# LOGIC.net
KiCad netlist of a schematic drawn in Altium Designer
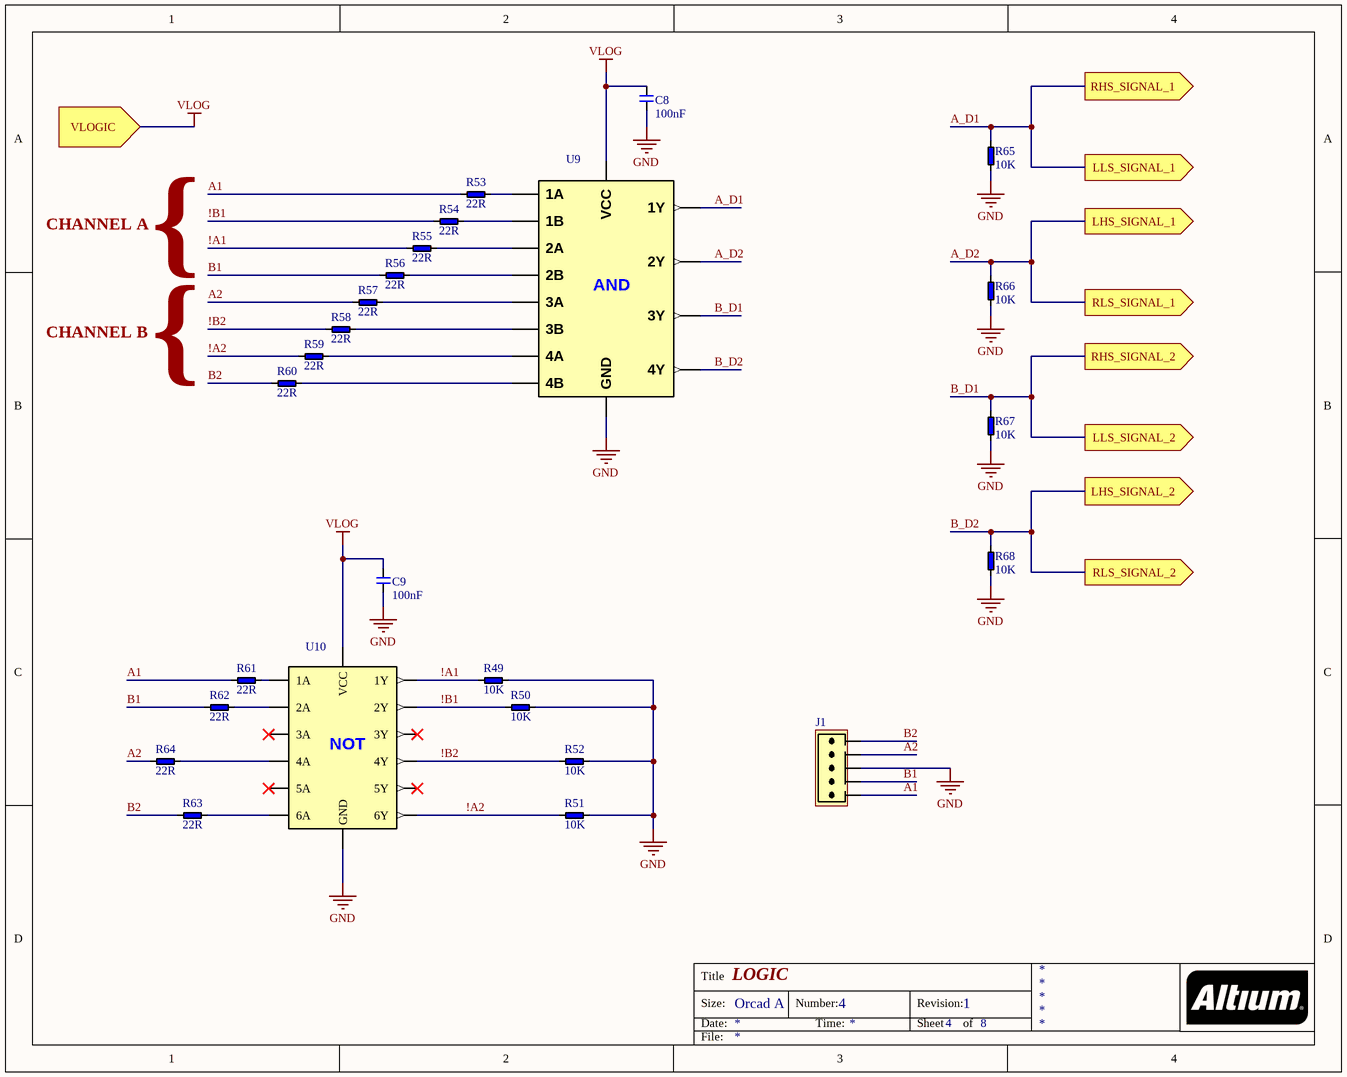
[diagram p0: LOGIC.SchDoc]

(export (version "E")
  (design (tool "Eeschema 10.0.6"))
  (components
    (comp (ref "C8")
      (value "100nF")
      (footprint "CCAP 0.1 N Y")
      (libsource (lib "Altium_Abbas") (part "CERAMIC CAP"))
    )
    (comp (ref "C9")
      (value "100nF")
      (footprint "CCAP 0.1 N Y")
      (libsource (lib "Altium_Abbas") (part "CERAMIC CAP"))
    )
    (comp (ref "J1")
      (value "DATA CONNECTOR *5")
      (footprint "MOLEX *5_DATA CONNECTOR")
      (description "Data Cable JST 5-pin")
      (libsource (lib "Altium_Abbas") (part "DATA CONNECTOR *5"))
    )
    (comp (ref "R49")
      (value "10K")
      (footprint "RESISTOR _9")
      (libsource (lib "Altium_Abbas") (part "RESISTOR"))
    )
    (comp (ref "R50")
      (value "10K")
      (footprint "RESISTOR _9")
      (libsource (lib "Altium_Abbas") (part "RESISTOR"))
    )
    (comp (ref "R51")
      (value "10K")
      (footprint "RESISTOR _9")
      (libsource (lib "Altium_Abbas") (part "RESISTOR"))
    )
    (comp (ref "R52")
      (value "10K")
      (footprint "RESISTOR _9")
      (libsource (lib "Altium_Abbas") (part "RESISTOR"))
    )
    (comp (ref "R53")
      (value "22R")
      (footprint "RESISTOR _9")
      (libsource (lib "Altium_Abbas") (part "RESISTOR"))
    )
    (comp (ref "R54")
      (value "22R")
      (footprint "RESISTOR _9")
      (libsource (lib "Altium_Abbas") (part "RESISTOR"))
    )
    (comp (ref "R55")
      (value "22R")
      (footprint "RESISTOR _9")
      (libsource (lib "Altium_Abbas") (part "RESISTOR"))
    )
    (comp (ref "R56")
      (value "22R")
      (footprint "RESISTOR _9")
      (libsource (lib "Altium_Abbas") (part "RESISTOR"))
    )
    (comp (ref "R57")
      (value "22R")
      (footprint "RESISTOR _9")
      (libsource (lib "Altium_Abbas") (part "RESISTOR"))
    )
    (comp (ref "R58")
      (value "22R")
      (footprint "RESISTOR _9")
      (libsource (lib "Altium_Abbas") (part "RESISTOR"))
    )
    (comp (ref "R59")
      (value "22R")
      (footprint "RESISTOR _9")
      (libsource (lib "Altium_Abbas") (part "RESISTOR"))
    )
    (comp (ref "R60")
      (value "22R")
      (footprint "RESISTOR _9")
      (libsource (lib "Altium_Abbas") (part "RESISTOR"))
    )
    (comp (ref "R61")
      (value "22R")
      (footprint "RESISTOR _9")
      (libsource (lib "Altium_Abbas") (part "RESISTOR"))
    )
    (comp (ref "R62")
      (value "22R")
      (footprint "RESISTOR _9")
      (libsource (lib "Altium_Abbas") (part "RESISTOR"))
    )
    (comp (ref "R63")
      (value "22R")
      (footprint "RESISTOR _9")
      (libsource (lib "Altium_Abbas") (part "RESISTOR"))
    )
    (comp (ref "R64")
      (value "22R")
      (footprint "RESISTOR _9")
      (libsource (lib "Altium_Abbas") (part "RESISTOR"))
    )
    (comp (ref "R65")
      (value "10K")
      (footprint "RESISTOR _9")
      (libsource (lib "Altium_Abbas") (part "RESISTOR"))
    )
    (comp (ref "R66")
      (value "10K")
      (footprint "RESISTOR _9")
      (libsource (lib "Altium_Abbas") (part "RESISTOR"))
    )
    (comp (ref "R67")
      (value "10K")
      (footprint "RESISTOR _9")
      (libsource (lib "Altium_Abbas") (part "RESISTOR"))
    )
    (comp (ref "R68")
      (value "10K")
      (footprint "RESISTOR _9")
      (libsource (lib "Altium_Abbas") (part "RESISTOR"))
    )
    (comp (ref "U9")
      (value "SN74F08N")
      (footprint "IC X14 PIN")
      (description "AND Gate 4-Element 2-IN Bipolar 14-Pin PDIP AND Gate 4-Element 2-IN Bipolar 14-Pin PDIP")
      (fields (field (name "MF") "Texas Instruments"))
      (libsource (lib "Altium_Abbas") (part "7408  (AND)"))
    )
    (comp (ref "U10")
      (value "SN7404N")
      (footprint "IC X14 PIN")
      (description "Inverter 6-Element Bipolar 14-Pin PDIP Tube")
      (fields (field (name "MF") "Texas Instruments"))
      (libsource (lib "Altium_Abbas") (part "7404  (NOT)"))
    )
  )
  (nets
    (net (code "1") (name "/!A1") (class "Default")
      (node (ref "R49") (pin "1") (pinfunction "5_1") (pintype "passive"))
      (node (ref "R55") (pin "1") (pinfunction "5_1") (pintype "passive"))
      (node (ref "U10") (pin "2") (pinfunction "1Y_2") (pintype "output"))
    )
    (net (code "2") (name "/!A2") (class "Default")
      (node (ref "R51") (pin "1") (pinfunction "5_1") (pintype "passive"))
      (node (ref "R59") (pin "1") (pinfunction "5_1") (pintype "passive"))
      (node (ref "U10") (pin "12") (pinfunction "6Y_12") (pintype "output"))
    )
    (net (code "3") (name "/!B1") (class "Default")
      (node (ref "R50") (pin "1") (pinfunction "5_1") (pintype "passive"))
      (node (ref "R54") (pin "1") (pinfunction "5_1") (pintype "passive"))
      (node (ref "U10") (pin "4") (pinfunction "2Y_4") (pintype "output"))
    )
    (net (code "4") (name "/!B2") (class "Default")
      (node (ref "R52") (pin "1") (pinfunction "5_1") (pintype "passive"))
      (node (ref "R58") (pin "1") (pinfunction "5_1") (pintype "passive"))
      (node (ref "U10") (pin "8") (pinfunction "4Y_8") (pintype "output"))
    )
    (net (code "5") (name "/A1") (class "Default")
      (node (ref "J1") (pin "5") (pinfunction "5_5") (pintype "passive"))
      (node (ref "R53") (pin "1") (pinfunction "5_1") (pintype "passive"))
      (node (ref "R61") (pin "1") (pinfunction "5_1") (pintype "passive"))
    )
    (net (code "6") (name "/A2") (class "Default")
      (node (ref "J1") (pin "2") (pinfunction "2_2") (pintype "passive"))
      (node (ref "R57") (pin "1") (pinfunction "5_1") (pintype "passive"))
      (node (ref "R64") (pin "1") (pinfunction "5_1") (pintype "passive"))
    )
    (net (code "7") (name "/A_D1") (class "Default")
      (node (ref "R65") (pin "2") (pinfunction "6_2") (pintype "passive"))
      (node (ref "U9") (pin "3") (pinfunction "1Y_3") (pintype "output"))
    )
    (net (code "8") (name "/A_D2") (class "Default")
      (node (ref "R66") (pin "2") (pinfunction "6_2") (pintype "passive"))
      (node (ref "U9") (pin "6") (pinfunction "2Y_6") (pintype "output"))
    )
    (net (code "9") (name "/B1") (class "Default")
      (node (ref "J1") (pin "4") (pinfunction "4_4") (pintype "passive"))
      (node (ref "R56") (pin "1") (pinfunction "5_1") (pintype "passive"))
      (node (ref "R62") (pin "1") (pinfunction "5_1") (pintype "passive"))
    )
    (net (code "10") (name "/B2") (class "Default")
      (node (ref "J1") (pin "1") (pinfunction "1_1") (pintype "passive"))
      (node (ref "R60") (pin "1") (pinfunction "5_1") (pintype "passive"))
      (node (ref "R63") (pin "1") (pinfunction "5_1") (pintype "passive"))
    )
    (net (code "11") (name "/B_D1") (class "Default")
      (node (ref "R67") (pin "2") (pinfunction "6_2") (pintype "passive"))
      (node (ref "U9") (pin "8") (pinfunction "3Y_8") (pintype "output"))
    )
    (net (code "12") (name "/B_D2") (class "Default")
      (node (ref "R68") (pin "2") (pinfunction "6_2") (pintype "passive"))
      (node (ref "U9") (pin "11") (pinfunction "4Y_11") (pintype "output"))
    )
    (net (code "13") (name "GND") (class "Default")
      (node (ref "C8") (pin "2") (pintype "passive"))
      (node (ref "C9") (pin "2") (pintype "passive"))
      (node (ref "J1") (pin "3") (pinfunction "3_3") (pintype "passive"))
      (node (ref "R49") (pin "2") (pinfunction "6_2") (pintype "passive"))
      (node (ref "R50") (pin "2") (pinfunction "6_2") (pintype "passive"))
      (node (ref "R51") (pin "2") (pinfunction "6_2") (pintype "passive"))
      (node (ref "R52") (pin "2") (pinfunction "6_2") (pintype "passive"))
      (node (ref "R65") (pin "1") (pinfunction "5_1") (pintype "passive"))
      (node (ref "R66") (pin "1") (pinfunction "5_1") (pintype "passive"))
      (node (ref "R67") (pin "1") (pinfunction "5_1") (pintype "passive"))
      (node (ref "R68") (pin "1") (pinfunction "5_1") (pintype "passive"))
      (node (ref "U10") (pin "7") (pinfunction "GND_7") (pintype "passive"))
      (node (ref "U9") (pin "7") (pinfunction "GND_7") (pintype "passive"))
    )
    (net (code "14") (name "Net-(R53-6)") (class "Default")
      (node (ref "R53") (pin "2") (pinfunction "6_2") (pintype "passive"))
      (node (ref "U9") (pin "1") (pinfunction "1A_1") (pintype "passive"))
    )
    (net (code "15") (name "Net-(R54-6)") (class "Default")
      (node (ref "R54") (pin "2") (pinfunction "6_2") (pintype "passive"))
      (node (ref "U9") (pin "2") (pinfunction "1B_2") (pintype "passive"))
    )
    (net (code "16") (name "Net-(R55-6)") (class "Default")
      (node (ref "R55") (pin "2") (pinfunction "6_2") (pintype "passive"))
      (node (ref "U9") (pin "4") (pinfunction "2A_4") (pintype "passive"))
    )
    (net (code "17") (name "Net-(R56-6)") (class "Default")
      (node (ref "R56") (pin "2") (pinfunction "6_2") (pintype "passive"))
      (node (ref "U9") (pin "5") (pinfunction "2B_5") (pintype "passive"))
    )
    (net (code "18") (name "Net-(R57-6)") (class "Default")
      (node (ref "R57") (pin "2") (pinfunction "6_2") (pintype "passive"))
      (node (ref "U9") (pin "9") (pinfunction "3A_9") (pintype "passive"))
    )
    (net (code "19") (name "Net-(R58-6)") (class "Default")
      (node (ref "R58") (pin "2") (pinfunction "6_2") (pintype "passive"))
      (node (ref "U9") (pin "10") (pinfunction "3B_10") (pintype "passive"))
    )
    (net (code "20") (name "Net-(R59-6)") (class "Default")
      (node (ref "R59") (pin "2") (pinfunction "6_2") (pintype "passive"))
      (node (ref "U9") (pin "12") (pinfunction "4A_12") (pintype "passive"))
    )
    (net (code "21") (name "Net-(R60-6)") (class "Default")
      (node (ref "R60") (pin "2") (pinfunction "6_2") (pintype "passive"))
      (node (ref "U9") (pin "13") (pinfunction "4B_13") (pintype "passive"))
    )
    (net (code "22") (name "Net-(R61-6)") (class "Default")
      (node (ref "R61") (pin "2") (pinfunction "6_2") (pintype "passive"))
      (node (ref "U10") (pin "1") (pinfunction "1A_1") (pintype "passive"))
    )
    (net (code "23") (name "Net-(R62-6)") (class "Default")
      (node (ref "R62") (pin "2") (pinfunction "6_2") (pintype "passive"))
      (node (ref "U10") (pin "3") (pinfunction "2A_3") (pintype "passive"))
    )
    (net (code "24") (name "Net-(R63-6)") (class "Default")
      (node (ref "R63") (pin "2") (pinfunction "6_2") (pintype "passive"))
      (node (ref "U10") (pin "13") (pinfunction "6A_13") (pintype "passive"))
    )
    (net (code "25") (name "Net-(R64-6)") (class "Default")
      (node (ref "R64") (pin "2") (pinfunction "6_2") (pintype "passive"))
      (node (ref "U10") (pin "9") (pinfunction "4A_9") (pintype "passive"))
    )
    (net (code "26") (name "VLOG") (class "Default")
      (node (ref "C8") (pin "1") (pintype "passive"))
      (node (ref "C9") (pin "1") (pintype "passive"))
      (node (ref "U10") (pin "14") (pinfunction "VCC_14") (pintype "passive"))
      (node (ref "U9") (pin "14") (pinfunction "VCC_14") (pintype "passive"))
    )
    (net (code "27") (name "unconnected-(U10-3A-Pad5)") (class "Default")
      (node (ref "U10") (pin "5") (pinfunction "3A_5") (pintype "passive+no_connect"))
    )
    (net (code "28") (name "unconnected-(U10-3Y-Pad6)") (class "Default")
      (node (ref "U10") (pin "6") (pinfunction "3Y_6") (pintype "output+no_connect"))
    )
    (net (code "29") (name "unconnected-(U10-5A-Pad11)") (class "Default")
      (node (ref "U10") (pin "11") (pinfunction "5A_11") (pintype "passive+no_connect"))
    )
    (net (code "30") (name "unconnected-(U10-5Y-Pad10)") (class "Default")
      (node (ref "U10") (pin "10") (pinfunction "5Y_10") (pintype "output+no_connect"))
    )
  )
)
